# data_interface.net
KiCad netlist of a schematic drawn in Altium Designer
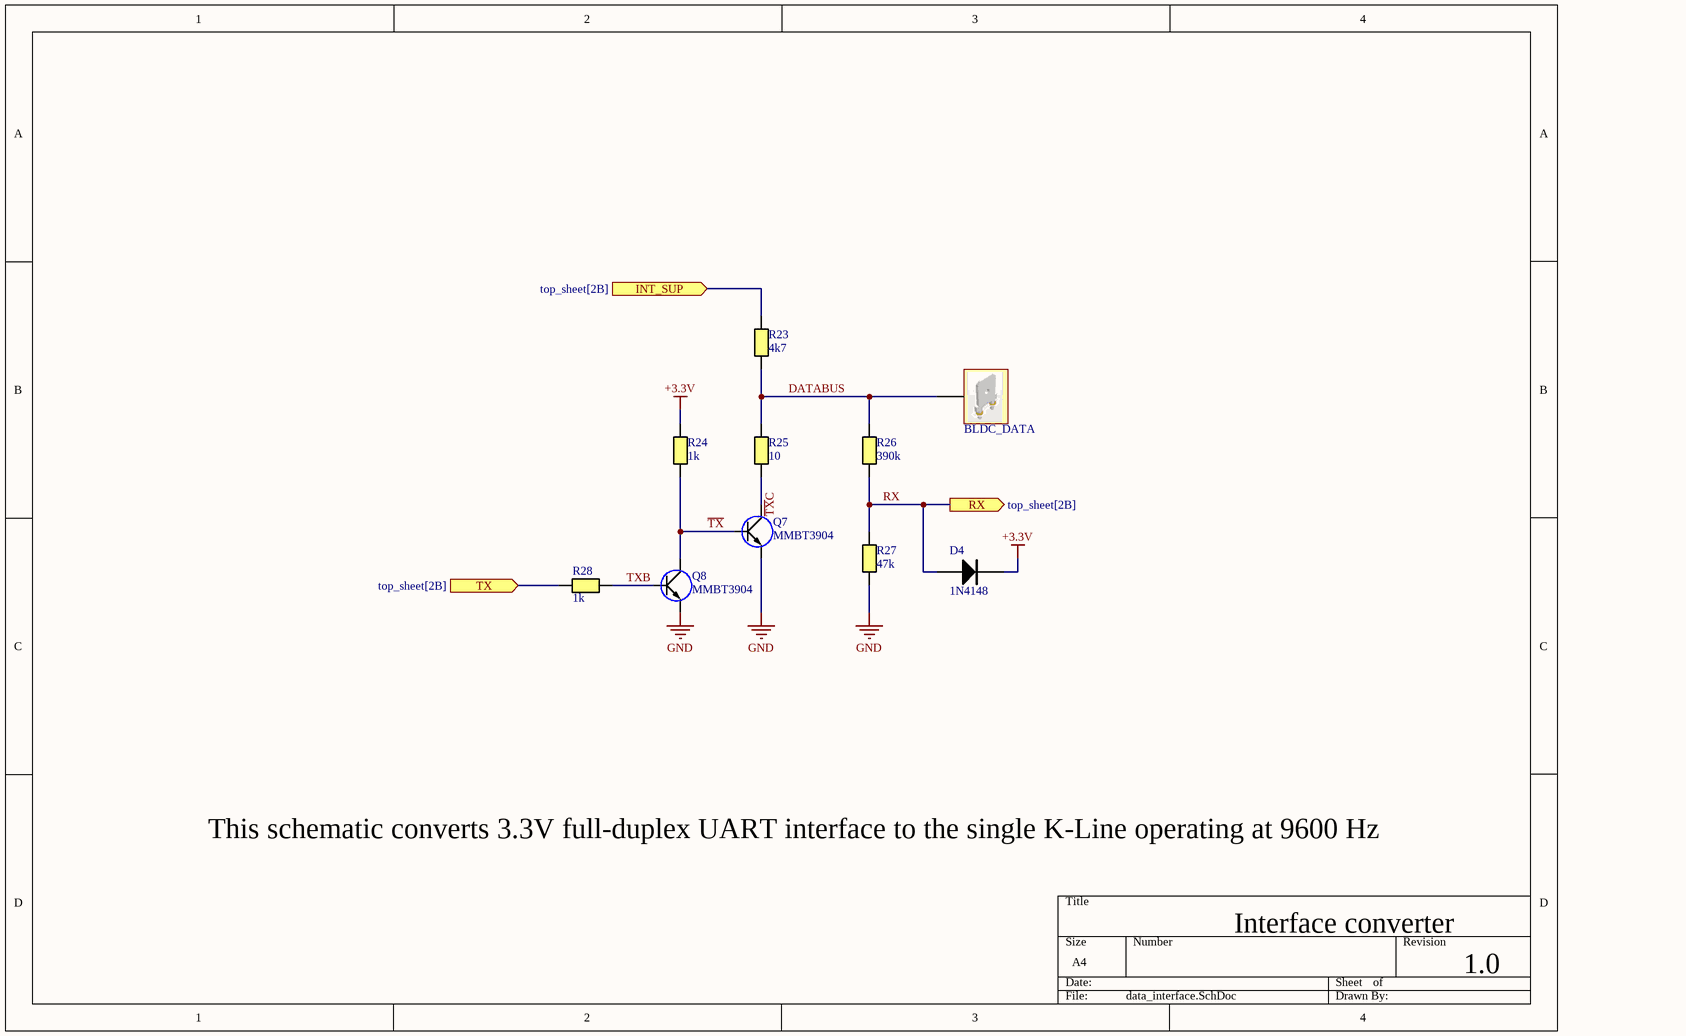
[diagram p0: data_interface.SchDoc]

(export (version "E")
  (design (tool "Eeschema 10.0.6"))
  (components
    (comp (ref "BLDC_DATA")
      (value "Crimp 6.3 single PCB")
      (footprint "Crimp 6.3mm single PCB")
      (description "Straight Mount Angle PCB Tab Terminal")
      (libsource (lib "Connectors") (part "Crimp 6.3 single PCB"))
    )
    (comp (ref "D4")
      (value "1N4148")
      (footprint "SOD80")
      (description "Small Signal Fast Switching Diodes")
      (libsource (lib "Diodes") (part "1N4148"))
    )
    (comp (ref "Q7")
      (value "MMBT3904")
      (footprint "SOT23")
      (description "NPN General Purpose Transistor")
      (libsource (lib "Transistors") (part "2N3904"))
    )
    (comp (ref "Q8")
      (value "MMBT3904")
      (footprint "SOT23")
      (description "NPN General Purpose Transistor")
      (libsource (lib "Transistors") (part "2N3904"))
    )
    (comp (ref "R23")
      (value "4k7")
      (footprint "RESC0603(1608)_N")
      (description "Resistor Medium Density")
      (libsource (lib "Discrete") (part "Resistor M"))
    )
    (comp (ref "R24")
      (value "1k")
      (footprint "RESC0603(1608)_N")
      (description "Resistor Medium Density")
      (libsource (lib "Discrete") (part "Resistor M"))
    )
    (comp (ref "R25")
      (value "10")
      (footprint "RESC0603(1608)_N")
      (description "Resistor Medium Density")
      (libsource (lib "Discrete") (part "Resistor M"))
    )
    (comp (ref "R26")
      (value "390k")
      (footprint "RESC0603(1608)_N")
      (description "Resistor Medium Density")
      (libsource (lib "Discrete") (part "Resistor M"))
    )
    (comp (ref "R27")
      (value "47k")
      (footprint "RESC0603(1608)_N")
      (description "Resistor Medium Density")
      (libsource (lib "Discrete") (part "Resistor M"))
    )
    (comp (ref "R28")
      (value "1k")
      (footprint "RESC0603(1608)_N")
      (description "Resistor Medium Density")
      (libsource (lib "") (part "Resistor M_1"))
    )
  )
  (nets
    (net (code "1") (name "+3.3V") (class "Default")
      (node (ref "D4") (pin "2") (pinfunction "K_2") (pintype "passive"))
      (node (ref "R24") (pin "2") (pinfunction "2_2") (pintype "passive"))
    )
    (net (code "2") (name "/DATABUS") (class "Default")
      (node (ref "BLDC_DATA") (pin "1") (pintype "passive"))
      (node (ref "R23") (pin "1") (pinfunction "1_1") (pintype "passive"))
      (node (ref "R25") (pin "2") (pinfunction "2_2") (pintype "passive"))
      (node (ref "R26") (pin "2") (pinfunction "2_2") (pintype "passive"))
    )
    (net (code "3") (name "/INT_SUP") (class "Default")
      (node (ref "R23") (pin "2") (pinfunction "2_2") (pintype "passive"))
    )
    (net (code "4") (name "/RX") (class "Default")
      (node (ref "D4") (pin "1") (pinfunction "A_1") (pintype "passive"))
      (node (ref "R26") (pin "1") (pinfunction "1_1") (pintype "passive"))
      (node (ref "R27") (pin "2") (pinfunction "2_2") (pintype "passive"))
    )
    (net (code "5") (name "/TX") (class "Default")
      (node (ref "R28") (pin "1") (pinfunction "1_1") (pintype "passive"))
    )
    (net (code "6") (name "/TXB") (class "Default")
      (node (ref "Q8") (pin "1") (pinfunction "B_1") (pintype "passive"))
      (node (ref "R28") (pin "2") (pinfunction "2_2") (pintype "passive"))
    )
    (net (code "7") (name "/~{TX}") (class "Default")
      (node (ref "Q7") (pin "1") (pinfunction "B_1") (pintype "passive"))
      (node (ref "Q8") (pin "3") (pinfunction "C_3") (pintype "passive"))
      (node (ref "R24") (pin "1") (pinfunction "1_1") (pintype "passive"))
    )
    (net (code "8") (name "/~{TX}C") (class "Default")
      (node (ref "Q7") (pin "3") (pinfunction "C_3") (pintype "passive"))
      (node (ref "R25") (pin "1") (pinfunction "1_1") (pintype "passive"))
    )
    (net (code "9") (name "GND") (class "Default")
      (node (ref "Q7") (pin "2") (pinfunction "E_2") (pintype "passive"))
      (node (ref "Q8") (pin "2") (pinfunction "E_2") (pintype "passive"))
      (node (ref "R27") (pin "1") (pinfunction "1_1") (pintype "passive"))
    )
  )
)
